# Power.net
KiCad netlist of a schematic drawn in Altium Designer
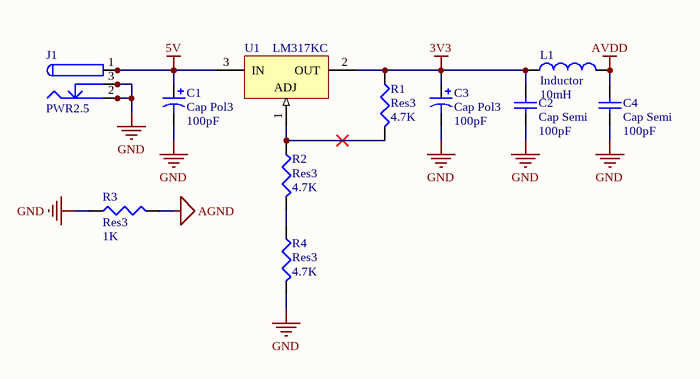
[diagram p0: Power.SchDoc]

(export (version "E")
  (design (tool "Eeschema 10.0.6"))
  (components
    (comp (ref "C1")
      (value "Cap Pol3")
      (footprint "C0805")
      (description "Polarized Capacitor (Surface Mount)")
      (fields (field (name "ALTIUM_VALUE") "100pF") (field (name "PUBLISHER") "Altium Limited"))
      (libsource (lib "Miscellaneous Devices") (part "Cap Pol3"))
    )
    (comp (ref "C2")
      (value "Cap Semi")
      (footprint "1608[0603]")
      (description "Capacitor (Semiconductor SIM Model)")
      (fields (field (name "ALTIUM_VALUE") "100pF") (field (name "PUBLISHER") "Altium Limited"))
      (libsource (lib "Miscellaneous Devices") (part "Cap Semi"))
    )
    (comp (ref "C3")
      (value "Cap Pol3")
      (footprint "C0805")
      (description "Polarized Capacitor (Surface Mount)")
      (fields (field (name "ALTIUM_VALUE") "100pF") (field (name "PUBLISHER") "Altium Limited"))
      (libsource (lib "Miscellaneous Devices") (part "Cap Pol3"))
    )
    (comp (ref "C4")
      (value "Cap Semi")
      (footprint "1608[0603]")
      (description "Capacitor (Semiconductor SIM Model)")
      (fields (field (name "ALTIUM_VALUE") "100pF") (field (name "PUBLISHER") "Altium Limited"))
      (libsource (lib "Miscellaneous Devices") (part "Cap Semi"))
    )
    (comp (ref "J1")
      (value "PWR2.5")
      (footprint "KLD-0202")
      (description "Low Voltage Power Supply Connector")
      (fields (field (name "PUBLISHER") "Altium Limited"))
      (libsource (lib "Miscellaneous Connectors") (part "PWR2.5"))
    )
    (comp (ref "L1")
      (value "Inductor")
      (footprint "0402-A")
      (fields (field (name "ALTIUM_VALUE") "10mH") (field (name "PUBLISHER") "Altium Limited"))
      (libsource (lib "Miscellaneous Devices") (part "Inductor"))
    )
    (comp (ref "R1")
      (value "Res3")
      (footprint "J1-0603")
      (description "Resistor")
      (fields (field (name "ALTIUM_VALUE") "4.7K") (field (name "PUBLISHER") "Altium Limited"))
      (libsource (lib "Miscellaneous Devices") (part "Res3"))
    )
    (comp (ref "R2")
      (value "Res3")
      (footprint "J1-0603")
      (description "Resistor")
      (fields (field (name "ALTIUM_VALUE") "4.7K") (field (name "PUBLISHER") "Altium Limited"))
      (libsource (lib "Miscellaneous Devices") (part "Res3"))
    )
    (comp (ref "R3")
      (value "Res3")
      (footprint "J1-0603")
      (description "Resistor")
      (fields (field (name "ALTIUM_VALUE") "1K") (field (name "PUBLISHER") "Altium Limited"))
      (libsource (lib "Miscellaneous Devices") (part "Res3"))
    )
    (comp (ref "R4")
      (value "Res3")
      (footprint "J1-0603")
      (description "Resistor")
      (fields (field (name "ALTIUM_VALUE") "4.7K") (field (name "PUBLISHER") "Altium Limited"))
      (libsource (lib "Miscellaneous Devices") (part "Res3"))
    )
    (comp (ref "U1")
      (value "LM317KC")
      (footprint "KC03")
      (description "3-Terminal Adjustable Regulator")
      (fields (field (name "PUBLISHER") "Altium Limited"))
      (libsource (lib "TI Power Mgt Voltage Regulator") (part "LM317KC"))
    )
  )
  (nets
    (net (code "1") (name "3V3") (class "Default")
      (node (ref "C2") (pin "2") (pinfunction "2_2") (pintype "passive"))
      (node (ref "C3") (pin "1") (pinfunction "1_1") (pintype "passive"))
      (node (ref "L1") (pin "1") (pinfunction "1_1") (pintype "passive"))
      (node (ref "R1") (pin "1") (pinfunction "1_1") (pintype "passive"))
      (node (ref "U1") (pin "2") (pinfunction "OUT_2") (pintype "power_in"))
    )
    (net (code "2") (name "5V") (class "Default")
      (node (ref "C1") (pin "1") (pinfunction "1_1") (pintype "passive"))
      (node (ref "J1") (pin "1") (pinfunction "1_1") (pintype "power_in"))
      (node (ref "J1") (pin "1A") (pinfunction "1A_1A") (pintype "power_in"))
      (node (ref "J1") (pin "1B") (pinfunction "1B_1B") (pintype "power_in"))
      (node (ref "U1") (pin "3") (pinfunction "IN_3") (pintype "power_in"))
    )
    (net (code "3") (name "AGND") (class "Default")
      (node (ref "R3") (pin "2") (pinfunction "2_2") (pintype "passive"))
    )
    (net (code "4") (name "AVDD") (class "Default")
      (node (ref "C4") (pin "2") (pinfunction "2_2") (pintype "passive"))
      (node (ref "L1") (pin "2") (pinfunction "2_2") (pintype "passive"))
    )
    (net (code "5") (name "GND") (class "Default")
      (node (ref "C1") (pin "2") (pinfunction "2_2") (pintype "passive"))
      (node (ref "C2") (pin "1") (pinfunction "1_1") (pintype "passive"))
      (node (ref "C3") (pin "2") (pinfunction "2_2") (pintype "passive"))
      (node (ref "C4") (pin "1") (pinfunction "1_1") (pintype "passive"))
      (node (ref "J1") (pin "2") (pinfunction "2_2") (pintype "power_in"))
      (node (ref "J1") (pin "2A") (pinfunction "2A_2A") (pintype "power_in"))
      (node (ref "J1") (pin "2B") (pinfunction "2B_2B") (pintype "power_in"))
      (node (ref "J1") (pin "3") (pinfunction "3_3") (pintype "power_in"))
      (node (ref "J1") (pin "3A") (pinfunction "3A_3A") (pintype "power_in"))
      (node (ref "J1") (pin "3B") (pinfunction "3B_3B") (pintype "power_in"))
      (node (ref "R3") (pin "1") (pinfunction "1_1") (pintype "passive"))
      (node (ref "R4") (pin "2") (pinfunction "2_2") (pintype "passive"))
    )
    (net (code "6") (name "Net-(R2-Pad2)") (class "Default")
      (node (ref "R2") (pin "2") (pinfunction "2_2") (pintype "passive"))
      (node (ref "R4") (pin "1") (pinfunction "1_1") (pintype "passive"))
    )
    (net (code "7") (name "Net-(U1-ADJ)") (class "Default")
      (node (ref "R1") (pin "2") (pinfunction "2_2") (pintype "passive"))
      (node (ref "R2") (pin "1") (pinfunction "1_1") (pintype "passive"))
      (node (ref "U1") (pin "1") (pinfunction "ADJ_1") (pintype "input"))
    )
  )
)
